# USB_2_0_CONTROLLER.net
KiCad netlist of a schematic drawn in Altium Designer
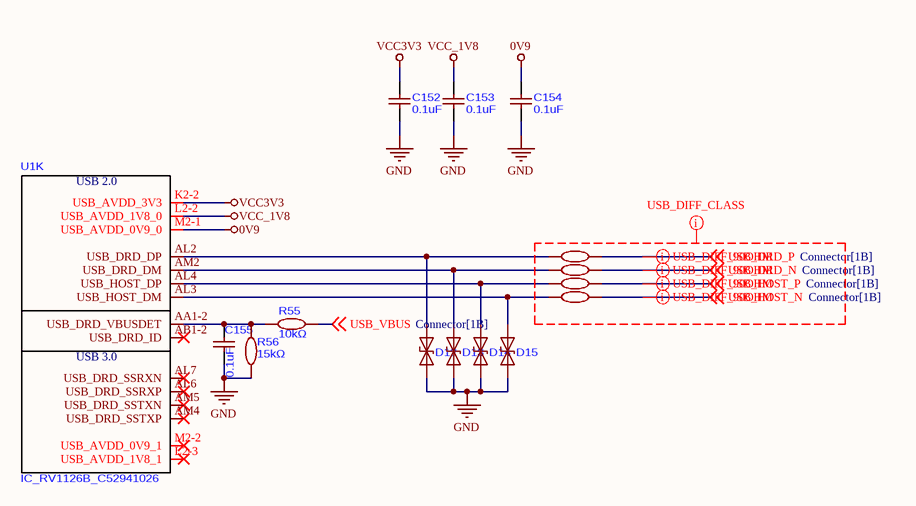
[diagram p0: USB 2.0 CONTROLLER.SchDoc]

(export (version "E")
  (design (tool "Eeschema 10.0.6"))
  (components
    (comp (ref "C152")
      (value "0.1uF")
      (footprint "C0201")
      (description "0.1uF ±10% 6.3V Ceramic Capacitor X5R 0201")
      (libsource (lib "Schlib1") (part "CAP_100nF-6.3V-10%-0201_1"))
    )
    (comp (ref "C153")
      (value "0.1uF")
      (footprint "C0201")
      (description "0.1uF ±10% 6.3V Ceramic Capacitor X5R 0201")
      (libsource (lib "Schlib1") (part "CAP_100nF-6.3V-10%-0201_1"))
    )
    (comp (ref "C154")
      (value "0.1uF")
      (footprint "C0201")
      (description "0.1uF ±10% 6.3V Ceramic Capacitor X5R 0201")
      (libsource (lib "Schlib1") (part "CAP_100nF-6.3V-10%-0201_1"))
    )
    (comp (ref "C155")
      (value "0.1uF")
      (footprint "C0201")
      (description "0.1uF ±10% 6.3V Ceramic Capacitor X5R 0201")
      (libsource (lib "Schlib1") (part "CAP_100nF-6.3V-10%-0201_1"))
    )
    (comp (ref "D12")
      (value "ESD DIODE")
      (footprint "DSN0603-2_L0.7-W0.3-P0.40-BI")
      (description "ESD DIODE 5VWM 5VC DSN0603-2 0.13PF")
      (libsource (lib "Schlib1") (part "PESD5V0H1BSFYL"))
    )
    (comp (ref "D13")
      (value "ESD DIODE")
      (footprint "DSN0603-2_L0.7-W0.3-P0.40-BI")
      (description "ESD DIODE 5VWM 5VC DSN0603-2 0.13PF")
      (libsource (lib "Schlib1") (part "PESD5V0H1BSFYL"))
    )
    (comp (ref "D14")
      (value "ESD DIODE")
      (footprint "DSN0603-2_L0.7-W0.3-P0.40-BI")
      (description "ESD DIODE 5VWM 5VC DSN0603-2 0.13PF")
      (libsource (lib "Schlib1") (part "PESD5V0H1BSFYL"))
    )
    (comp (ref "D15")
      (value "ESD DIODE")
      (footprint "DSN0603-2_L0.7-W0.3-P0.40-BI")
      (description "ESD DIODE 5VWM 5VC DSN0603-2 0.13PF")
      (libsource (lib "Schlib1") (part "PESD5V0H1BSFYL"))
    )
    (comp (ref "R51")
      (value "2.2Ω")
      (footprint "R0201")
      (description "RES 2.2Ω ±1% 50mW 0201")
      (libsource (lib "Schlib1") (part "RES_2.2-50mW-1%-0201"))
    )
    (comp (ref "R52")
      (value "2.2Ω")
      (footprint "R0201")
      (description "RES 2.2Ω ±1% 50mW 0201")
      (libsource (lib "Schlib1") (part "RES_2.2-50mW-1%-0201"))
    )
    (comp (ref "R53")
      (value "2.2Ω")
      (footprint "R0201")
      (description "RES 2.2Ω ±1% 50mW 0201")
      (libsource (lib "Schlib1") (part "RES_2.2-50mW-1%-0201"))
    )
    (comp (ref "R54")
      (value "2.2Ω")
      (footprint "R0201")
      (description "RES 2.2Ω ±1% 50mW 0201")
      (libsource (lib "Schlib1") (part "RES_2.2-50mW-1%-0201"))
    )
    (comp (ref "R55")
      (value "10kΩ")
      (footprint "R0201")
      (description "RES 10KΩ ±1% 50mW 0201")
      (libsource (lib "Schlib1") (part "RES_10K-50mW-1%-0201"))
    )
    (comp (ref "R56")
      (value "15kΩ")
      (footprint "R0201")
      (description "RES 15kΩ ±1% 50mW 0201")
      (libsource (lib "Schlib1") (part "RES_15K-0.05W-1%-0201"))
    )
    (comp (ref "U1")
      (value "IC_RV1126B_C52941026")
      (footprint "CCSP-491_L14.0-W14.0-TL_RV1126B")
      (libsource (lib "Schlib1") (part "IC_RV1126B_C52941026"))
    )
  )
  (nets
    (net (code "1") (name "0V9") (class "Default")
      (node (ref "C154") (pin "2") (pinfunction "2_2") (pintype "passive"))
      (node (ref "U1") (pin "M2-1") (pinfunction "USB_AVDD_0V9_0_M2-1") (pintype "passive"))
    )
    (net (code "2") (name "GND") (class "Default")
      (node (ref "C152") (pin "1") (pinfunction "1_1") (pintype "passive"))
      (node (ref "C153") (pin "1") (pinfunction "1_1") (pintype "passive"))
      (node (ref "C154") (pin "1") (pinfunction "1_1") (pintype "passive"))
      (node (ref "C155") (pin "1") (pinfunction "1_1") (pintype "passive"))
      (node (ref "D12") (pin "1") (pinfunction "K_1") (pintype "passive"))
      (node (ref "D13") (pin "1") (pinfunction "K_1") (pintype "passive"))
      (node (ref "D14") (pin "1") (pinfunction "K_1") (pintype "passive"))
      (node (ref "D15") (pin "1") (pinfunction "K_1") (pintype "passive"))
      (node (ref "R56") (pin "1") (pinfunction "1_1") (pintype "passive"))
    )
    (net (code "3") (name "Net-(D12-A)") (class "Default")
      (node (ref "D12") (pin "2") (pinfunction "A_2") (pintype "passive"))
      (node (ref "R51") (pin "1") (pinfunction "1_1") (pintype "passive"))
      (node (ref "U1") (pin "AL2") (pinfunction "USB_DRD_DP_AL2") (pintype "passive"))
    )
    (net (code "4") (name "Net-(D13-A)") (class "Default")
      (node (ref "D13") (pin "2") (pinfunction "A_2") (pintype "passive"))
      (node (ref "R52") (pin "1") (pinfunction "1_1") (pintype "passive"))
      (node (ref "U1") (pin "AM2") (pinfunction "USB_DRD_DM_AM2") (pintype "passive"))
    )
    (net (code "5") (name "Net-(D14-A)") (class "Default")
      (node (ref "D14") (pin "2") (pinfunction "A_2") (pintype "passive"))
      (node (ref "R53") (pin "1") (pinfunction "1_1") (pintype "passive"))
      (node (ref "U1") (pin "AL4") (pinfunction "USB_HOST_DP_AL4") (pintype "passive"))
    )
    (net (code "6") (name "Net-(D15-A)") (class "Default")
      (node (ref "D15") (pin "2") (pinfunction "A_2") (pintype "passive"))
      (node (ref "R54") (pin "1") (pinfunction "1_1") (pintype "passive"))
      (node (ref "U1") (pin "AL3") (pinfunction "USB_HOST_DM_AL3") (pintype "passive"))
    )
    (net (code "7") (name "Net-(U1K-USB_DRD_VBUSDET)") (class "Default")
      (node (ref "C155") (pin "2") (pinfunction "2_2") (pintype "passive"))
      (node (ref "R55") (pin "1") (pinfunction "1_1") (pintype "passive"))
      (node (ref "R56") (pin "2") (pinfunction "2_2") (pintype "passive"))
      (node (ref "U1") (pin "AA1-2") (pinfunction "USB_DRD_VBUSDET_AA1-2") (pintype "passive"))
    )
    (net (code "8") (name "USB_DRD_N") (class "Default")
      (node (ref "R52") (pin "2") (pinfunction "2_2") (pintype "passive"))
    )
    (net (code "9") (name "USB_DRD_P") (class "Default")
      (node (ref "R51") (pin "2") (pinfunction "2_2") (pintype "passive"))
    )
    (net (code "10") (name "USB_HOST_N") (class "Default")
      (node (ref "R54") (pin "2") (pinfunction "2_2") (pintype "passive"))
    )
    (net (code "11") (name "USB_HOST_P") (class "Default")
      (node (ref "R53") (pin "2") (pinfunction "2_2") (pintype "passive"))
    )
    (net (code "12") (name "USB_VBUS") (class "Default")
      (node (ref "R55") (pin "2") (pinfunction "2_2") (pintype "passive"))
    )
    (net (code "13") (name "VCC3V3") (class "Default")
      (node (ref "C152") (pin "2") (pinfunction "2_2") (pintype "passive"))
      (node (ref "U1") (pin "K2-2") (pinfunction "USB_AVDD_3V3_K2-2") (pintype "passive"))
    )
    (net (code "14") (name "VCC_1V8") (class "Default")
      (node (ref "C153") (pin "2") (pinfunction "2_2") (pintype "passive"))
      (node (ref "U1") (pin "L2-2") (pinfunction "USB_AVDD_1V8_0_L2-2") (pintype "passive"))
    )
    (net (code "15") (name "unconnected-(U1K-USB_AVDD_0V9_1-PadM2-2)") (class "Default")
      (node (ref "U1") (pin "M2-2") (pinfunction "USB_AVDD_0V9_1_M2-2") (pintype "passive+no_connect"))
    )
    (net (code "16") (name "unconnected-(U1K-USB_AVDD_1V8_1-PadL2-3)") (class "Default")
      (node (ref "U1") (pin "L2-3") (pinfunction "USB_AVDD_1V8_1_L2-3") (pintype "passive+no_connect"))
    )
    (net (code "17") (name "unconnected-(U1K-USB_DRD_ID-PadAB1-2)") (class "Default")
      (node (ref "U1") (pin "AB1-2") (pinfunction "USB_DRD_ID_AB1-2") (pintype "passive+no_connect"))
    )
    (net (code "18") (name "unconnected-(U1K-USB_DRD_SSRXN-PadAL7)") (class "Default")
      (node (ref "U1") (pin "AL7") (pinfunction "USB_DRD_SSRXN_AL7") (pintype "passive+no_connect"))
    )
    (net (code "19") (name "unconnected-(U1K-USB_DRD_SSRXP-PadAL6)") (class "Default")
      (node (ref "U1") (pin "AL6") (pinfunction "USB_DRD_SSRXP_AL6") (pintype "passive+no_connect"))
    )
    (net (code "20") (name "unconnected-(U1K-USB_DRD_SSTXN-PadAM5)") (class "Default")
      (node (ref "U1") (pin "AM5") (pinfunction "USB_DRD_SSTXN_AM5") (pintype "passive+no_connect"))
    )
    (net (code "21") (name "unconnected-(U1K-USB_DRD_SSTXP-PadAM4)") (class "Default")
      (node (ref "U1") (pin "AM4") (pinfunction "USB_DRD_SSTXP_AM4") (pintype "passive+no_connect"))
    )
  )
)
